# lfo.net
KiCad netlist of a schematic drawn in EAGLE
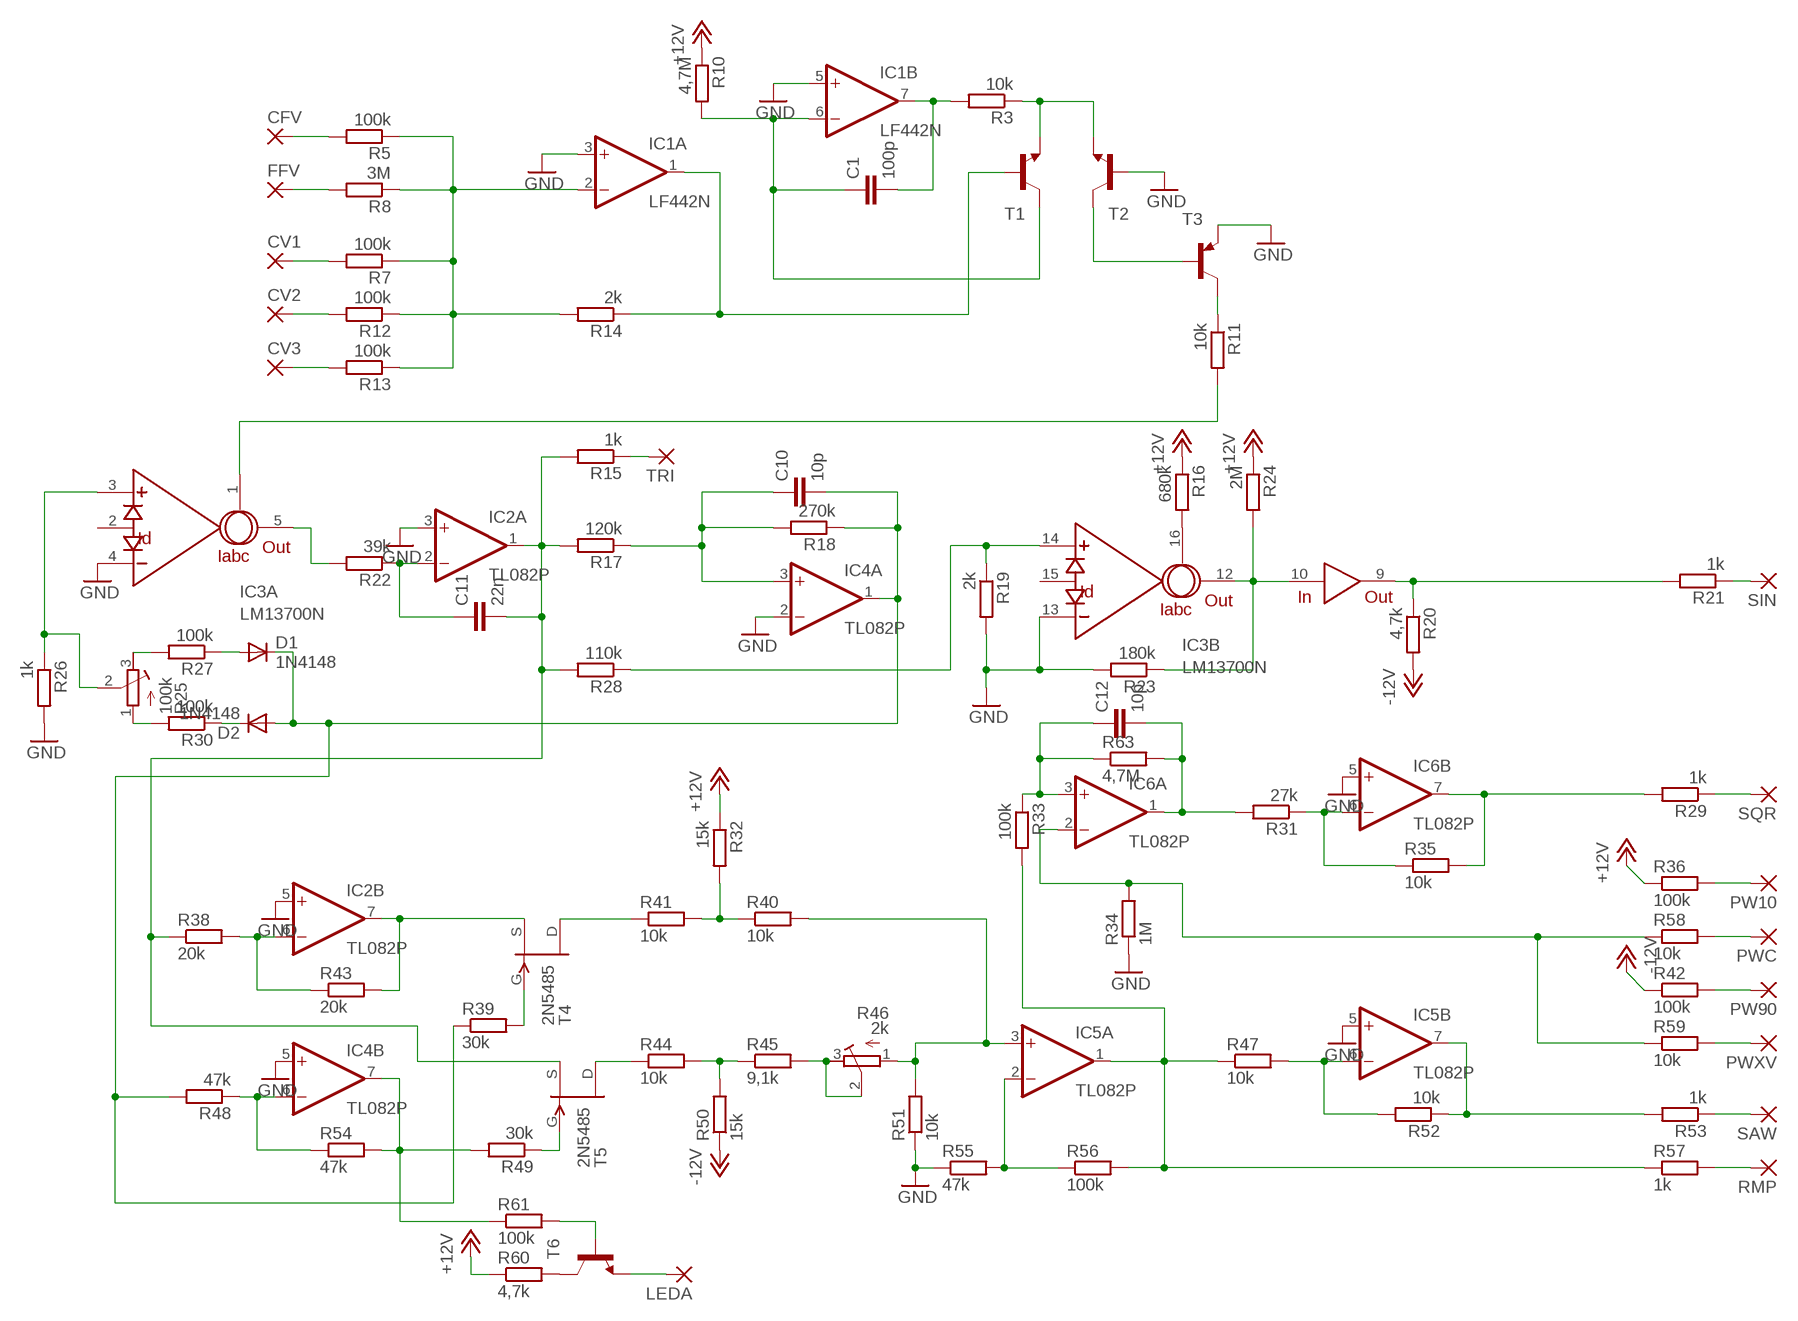
[diagram p0: schematic, sheet 1]
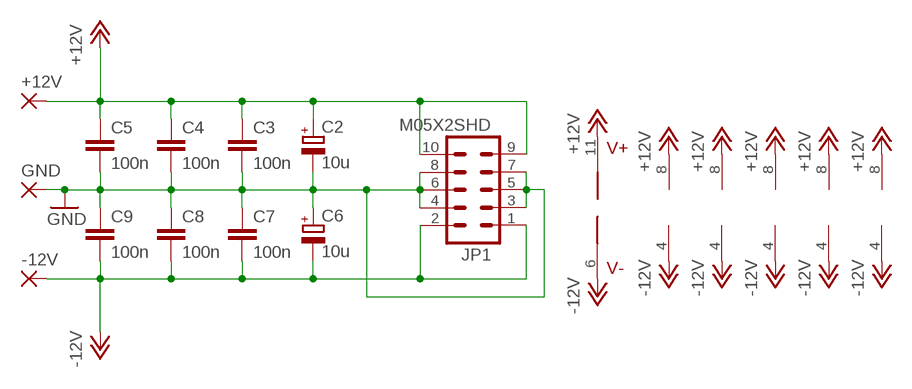
[diagram p1: schematic, sheet 2]

(export (version "E")
  (design (tool "Eeschema 10.0.6"))
  (components
    (comp (ref "+12V")
      (value "2,54/1,0")
      (footprint "eagle-import:2,54_1,0")
      (libsource (lib "eagle-import") (part "2,54/1,0"))
    )
    (comp (ref "-12V")
      (value "2,54/1,0")
      (footprint "eagle-import:2,54_1,0")
      (libsource (lib "eagle-import") (part "2,54/1,0"))
    )
    (comp (ref "C2")
      (value "10u")
      (footprint "eagle-import:E3,5-8")
      (libsource (lib "eagle-import") (part "CPOL-EUE3.5-8"))
    )
    (comp (ref "C3")
      (value "100n")
      (footprint "eagle-import:C050-035X075")
      (libsource (lib "eagle-import") (part "C-EU050-035X075"))
    )
    (comp (ref "C4")
      (value "100n")
      (footprint "eagle-import:C050-035X075")
      (libsource (lib "eagle-import") (part "C-EU050-035X075"))
    )
    (comp (ref "C5")
      (value "100n")
      (footprint "eagle-import:C050-035X075")
      (libsource (lib "eagle-import") (part "C-EU050-035X075"))
    )
    (comp (ref "C6")
      (value "10u")
      (footprint "eagle-import:E3,5-8")
      (libsource (lib "eagle-import") (part "CPOL-EUE3.5-8"))
    )
    (comp (ref "C7")
      (value "100n")
      (footprint "eagle-import:C050-035X075")
      (libsource (lib "eagle-import") (part "C-EU050-035X075"))
    )
    (comp (ref "C8")
      (value "100n")
      (footprint "eagle-import:C050-035X075")
      (libsource (lib "eagle-import") (part "C-EU050-035X075"))
    )
    (comp (ref "C9")
      (value "100n")
      (footprint "eagle-import:C050-035X075")
      (libsource (lib "eagle-import") (part "C-EU050-035X075"))
    )
    (comp (ref "GND")
      (value "2,54/1,0")
      (footprint "eagle-import:2,54_1,0")
      (libsource (lib "eagle-import") (part "2,54/1,0"))
    )
    (comp (ref "IC1")
      (value "LF442N")
      (footprint "eagle-import:DIL08")
      (libsource (lib "eagle-import") (part "LF442N"))
    )
    (comp (ref "IC2")
      (value "TL082P")
      (footprint "eagle-import:DIL08")
      (libsource (lib "eagle-import") (part "TL082P"))
    )
    (comp (ref "IC3")
      (value "LM13700N")
      (footprint "eagle-import:DIL16")
      (libsource (lib "eagle-import") (part "LM13700N"))
    )
    (comp (ref "IC4")
      (value "TL082P")
      (footprint "eagle-import:DIL08")
      (libsource (lib "eagle-import") (part "TL082P"))
    )
    (comp (ref "IC5")
      (value "TL082P")
      (footprint "eagle-import:DIL08")
      (libsource (lib "eagle-import") (part "TL082P"))
    )
    (comp (ref "IC6")
      (value "TL082P")
      (footprint "eagle-import:DIL08")
      (libsource (lib "eagle-import") (part "TL082P"))
    )
    (comp (ref "JP1")
      (value "M05X2SHD")
      (footprint "eagle-import:2X5-SHROUDED")
      (libsource (lib "eagle-import") (part "M05X2SHD"))
    )
    (comp (ref "C1")
      (value "100p")
      (footprint "eagle-import:C050-035X075")
      (libsource (lib "eagle-import") (part "C-EU050-035X075"))
    )
    (comp (ref "C10")
      (value "10p")
      (footprint "eagle-import:C050-035X075")
      (libsource (lib "eagle-import") (part "C-EU050-035X075"))
    )
    (comp (ref "C11")
      (value "22n")
      (footprint "eagle-import:C050-035X075")
      (libsource (lib "eagle-import") (part "C-EU050-035X075"))
    )
    (comp (ref "C12")
      (value "10p")
      (footprint "eagle-import:C050-035X075")
      (libsource (lib "eagle-import") (part "C-EU050-035X075"))
    )
    (comp (ref "CFV")
      (value "2,54/1,0")
      (footprint "eagle-import:2,54_1,0")
      (libsource (lib "eagle-import") (part "2,54/1,0"))
    )
    (comp (ref "CV1")
      (value "2,54/1,0")
      (footprint "eagle-import:2,54_1,0")
      (libsource (lib "eagle-import") (part "2,54/1,0"))
    )
    (comp (ref "CV2")
      (value "2,54/1,0")
      (footprint "eagle-import:2,54_1,0")
      (libsource (lib "eagle-import") (part "2,54/1,0"))
    )
    (comp (ref "CV3")
      (value "2,54/1,0")
      (footprint "eagle-import:2,54_1,0")
      (libsource (lib "eagle-import") (part "2,54/1,0"))
    )
    (comp (ref "D1")
      (value "1N4148")
      (footprint "eagle-import:DO35-7")
      (libsource (lib "eagle-import") (part "1N4148DO35-7"))
    )
    (comp (ref "D2")
      (value "1N4148")
      (footprint "eagle-import:DO35-7")
      (libsource (lib "eagle-import") (part "1N4148DO35-7"))
    )
    (comp (ref "FFV")
      (value "2,54/1,0")
      (footprint "eagle-import:2,54_1,0")
      (libsource (lib "eagle-import") (part "2,54/1,0"))
    )
    (comp (ref "LEDA")
      (value "2,54/1,0")
      (footprint "eagle-import:2,54_1,0")
      (libsource (lib "eagle-import") (part "2,54/1,0"))
    )
    (comp (ref "PW10")
      (value "2,54/1,0")
      (footprint "eagle-import:2,54_1,0")
      (libsource (lib "eagle-import") (part "2,54/1,0"))
    )
    (comp (ref "PW90")
      (value "2,54/1,0")
      (footprint "eagle-import:2,54_1,0")
      (libsource (lib "eagle-import") (part "2,54/1,0"))
    )
    (comp (ref "PWC")
      (value "2,54/1,0")
      (footprint "eagle-import:2,54_1,0")
      (libsource (lib "eagle-import") (part "2,54/1,0"))
    )
    (comp (ref "PWXV")
      (value "2,54/1,0")
      (footprint "eagle-import:2,54_1,0")
      (libsource (lib "eagle-import") (part "2,54/1,0"))
    )
    (comp (ref "R3")
      (value "10k")
      (footprint "eagle-import:0309V")
      (libsource (lib "eagle-import") (part "R-EU_0309/V"))
    )
    (comp (ref "R5")
      (value "100k")
      (footprint "eagle-import:0309V")
      (libsource (lib "eagle-import") (part "R-EU_0309/V"))
    )
    (comp (ref "R7")
      (value "100k")
      (footprint "eagle-import:0309V")
      (libsource (lib "eagle-import") (part "R-EU_0309/V"))
    )
    (comp (ref "R8")
      (value "3M")
      (footprint "eagle-import:0309V")
      (libsource (lib "eagle-import") (part "R-EU_0309/V"))
    )
    (comp (ref "R10")
      (value "4,7M")
      (footprint "eagle-import:0309V")
      (libsource (lib "eagle-import") (part "R-EU_0309/V"))
    )
    (comp (ref "R11")
      (value "10k")
      (footprint "eagle-import:0309V")
      (libsource (lib "eagle-import") (part "R-EU_0309/V"))
    )
    (comp (ref "R12")
      (value "100k")
      (footprint "eagle-import:0309V")
      (libsource (lib "eagle-import") (part "R-EU_0309/V"))
    )
    (comp (ref "R13")
      (value "100k")
      (footprint "eagle-import:0309V")
      (libsource (lib "eagle-import") (part "R-EU_0309/V"))
    )
    (comp (ref "R14")
      (value "2k")
      (footprint "eagle-import:0309V")
      (libsource (lib "eagle-import") (part "R-EU_0309/V"))
    )
    (comp (ref "R15")
      (value "1k")
      (footprint "eagle-import:0309V")
      (libsource (lib "eagle-import") (part "R-EU_0309/V"))
    )
    (comp (ref "R16")
      (value "680k")
      (footprint "eagle-import:0309V")
      (libsource (lib "eagle-import") (part "R-EU_0309/V"))
    )
    (comp (ref "R17")
      (value "120k")
      (footprint "eagle-import:0309V")
      (libsource (lib "eagle-import") (part "R-EU_0309/V"))
    )
    (comp (ref "R18")
      (value "270k")
      (footprint "eagle-import:0309V")
      (libsource (lib "eagle-import") (part "R-EU_0309/V"))
    )
    (comp (ref "R19")
      (value "2k")
      (footprint "eagle-import:0309V")
      (libsource (lib "eagle-import") (part "R-EU_0309/V"))
    )
    (comp (ref "R20")
      (value "4,7k")
      (footprint "eagle-import:0309V")
      (libsource (lib "eagle-import") (part "R-EU_0309/V"))
    )
    (comp (ref "R21")
      (value "1k")
      (footprint "eagle-import:0309V")
      (libsource (lib "eagle-import") (part "R-EU_0309/V"))
    )
    (comp (ref "R22")
      (value "39k")
      (footprint "eagle-import:0309V")
      (libsource (lib "eagle-import") (part "R-EU_0309/V"))
    )
    (comp (ref "R23")
      (value "180k")
      (footprint "eagle-import:0309V")
      (libsource (lib "eagle-import") (part "R-EU_0309/V"))
    )
    (comp (ref "R24")
      (value "2M")
      (footprint "eagle-import:0309V")
      (libsource (lib "eagle-import") (part "R-EU_0309/V"))
    )
    (comp (ref "R25")
      (value "100k")
      (footprint "eagle-import:RTRIM64W")
      (libsource (lib "eagle-import") (part "R-TRIMM64W"))
    )
    (comp (ref "R26")
      (value "1k")
      (footprint "eagle-import:0309V")
      (libsource (lib "eagle-import") (part "R-EU_0309/V"))
    )
    (comp (ref "R27")
      (value "100k")
      (footprint "eagle-import:0309V")
      (libsource (lib "eagle-import") (part "R-EU_0309/V"))
    )
    (comp (ref "R28")
      (value "110k")
      (footprint "eagle-import:0309V")
      (libsource (lib "eagle-import") (part "R-EU_0309/V"))
    )
    (comp (ref "R29")
      (value "1k")
      (footprint "eagle-import:0309V")
      (libsource (lib "eagle-import") (part "R-EU_0309/V"))
    )
    (comp (ref "R30")
      (value "100k")
      (footprint "eagle-import:0309V")
      (libsource (lib "eagle-import") (part "R-EU_0309/V"))
    )
    (comp (ref "R31")
      (value "27k")
      (footprint "eagle-import:0309V")
      (libsource (lib "eagle-import") (part "R-EU_0309/V"))
    )
    (comp (ref "R32")
      (value "15k")
      (footprint "eagle-import:0309V")
      (libsource (lib "eagle-import") (part "R-EU_0309/V"))
    )
    (comp (ref "R33")
      (value "100k")
      (footprint "eagle-import:0309V")
      (libsource (lib "eagle-import") (part "R-EU_0309/V"))
    )
    (comp (ref "R34")
      (value "1M")
      (footprint "eagle-import:0309V")
      (libsource (lib "eagle-import") (part "R-EU_0309/V"))
    )
    (comp (ref "R35")
      (value "10k")
      (footprint "eagle-import:0309V")
      (libsource (lib "eagle-import") (part "R-EU_0309/V"))
    )
    (comp (ref "R36")
      (value "100k")
      (footprint "eagle-import:0309V")
      (libsource (lib "eagle-import") (part "R-EU_0309/V"))
    )
    (comp (ref "R38")
      (value "20k")
      (footprint "eagle-import:0309V")
      (libsource (lib "eagle-import") (part "R-EU_0309/V"))
    )
    (comp (ref "R39")
      (value "30k")
      (footprint "eagle-import:0309V")
      (libsource (lib "eagle-import") (part "R-EU_0309/V"))
    )
    (comp (ref "R40")
      (value "10k")
      (footprint "eagle-import:0309V")
      (libsource (lib "eagle-import") (part "R-EU_0309/V"))
    )
    (comp (ref "R41")
      (value "10k")
      (footprint "eagle-import:0309V")
      (libsource (lib "eagle-import") (part "R-EU_0309/V"))
    )
    (comp (ref "R42")
      (value "100k")
      (footprint "eagle-import:0309V")
      (libsource (lib "eagle-import") (part "R-EU_0309/V"))
    )
    (comp (ref "R43")
      (value "20k")
      (footprint "eagle-import:0309V")
      (libsource (lib "eagle-import") (part "R-EU_0309/V"))
    )
    (comp (ref "R44")
      (value "10k")
      (footprint "eagle-import:0309V")
      (libsource (lib "eagle-import") (part "R-EU_0309/V"))
    )
    (comp (ref "R45")
      (value "9,1k")
      (footprint "eagle-import:0309V")
      (libsource (lib "eagle-import") (part "R-EU_0309/V"))
    )
    (comp (ref "R46")
      (value "2k")
      (footprint "eagle-import:RTRIM64W")
      (libsource (lib "eagle-import") (part "R-TRIMM64W"))
    )
    (comp (ref "R47")
      (value "10k")
      (footprint "eagle-import:0309V")
      (libsource (lib "eagle-import") (part "R-EU_0309/V"))
    )
    (comp (ref "R48")
      (value "47k")
      (footprint "eagle-import:0309V")
      (libsource (lib "eagle-import") (part "R-EU_0309/V"))
    )
    (comp (ref "R49")
      (value "30k")
      (footprint "eagle-import:0309V")
      (libsource (lib "eagle-import") (part "R-EU_0309/V"))
    )
    (comp (ref "R50")
      (value "15k")
      (footprint "eagle-import:0309V")
      (libsource (lib "eagle-import") (part "R-EU_0309/V"))
    )
    (comp (ref "R51")
      (value "10k")
      (footprint "eagle-import:0309V")
      (libsource (lib "eagle-import") (part "R-EU_0309/V"))
    )
    (comp (ref "R52")
      (value "10k")
      (footprint "eagle-import:0309V")
      (libsource (lib "eagle-import") (part "R-EU_0309/V"))
    )
    (comp (ref "R53")
      (value "1k")
      (footprint "eagle-import:0309V")
      (libsource (lib "eagle-import") (part "R-EU_0309/V"))
    )
    (comp (ref "R54")
      (value "47k")
      (footprint "eagle-import:0309V")
      (libsource (lib "eagle-import") (part "R-EU_0309/V"))
    )
    (comp (ref "R55")
      (value "47k")
      (footprint "eagle-import:0309V")
      (libsource (lib "eagle-import") (part "R-EU_0309/V"))
    )
    (comp (ref "R56")
      (value "100k")
      (footprint "eagle-import:0309V")
      (libsource (lib "eagle-import") (part "R-EU_0309/V"))
    )
    (comp (ref "R57")
      (value "1k")
      (footprint "eagle-import:0309V")
      (libsource (lib "eagle-import") (part "R-EU_0309/V"))
    )
    (comp (ref "R58")
      (value "10k")
      (footprint "eagle-import:0309V")
      (libsource (lib "eagle-import") (part "R-EU_0309/V"))
    )
    (comp (ref "R59")
      (value "10k")
      (footprint "eagle-import:0309V")
      (libsource (lib "eagle-import") (part "R-EU_0309/V"))
    )
    (comp (ref "R60")
      (value "4,7k")
      (footprint "eagle-import:0309V")
      (libsource (lib "eagle-import") (part "R-EU_0309/V"))
    )
    (comp (ref "R61")
      (value "100k")
      (footprint "eagle-import:0309V")
      (libsource (lib "eagle-import") (part "R-EU_0309/V"))
    )
    (comp (ref "R63")
      (value "4,7M")
      (footprint "eagle-import:0309_10")
      (libsource (lib "eagle-import") (part "R-EU_0309/10"))
    )
    (comp (ref "RMP")
      (value "2,54/1,0")
      (footprint "eagle-import:2,54_1,0")
      (libsource (lib "eagle-import") (part "2,54/1,0"))
    )
    (comp (ref "SAW")
      (value "2,54/1,0")
      (footprint "eagle-import:2,54_1,0")
      (libsource (lib "eagle-import") (part "2,54/1,0"))
    )
    (comp (ref "SIN")
      (value "2,54/1,0")
      (footprint "eagle-import:2,54_1,0")
      (libsource (lib "eagle-import") (part "2,54/1,0"))
    )
    (comp (ref "SQR")
      (value "2,54/1,0")
      (footprint "eagle-import:2,54_1,0")
      (libsource (lib "eagle-import") (part "2,54/1,0"))
    )
    (comp (ref "T1")
      (value "2N3904-NPN-TO92-EBC")
      (footprint "eagle-import:TO92-EBC")
      (libsource (lib "eagle-import") (part "-NPN-TO92-EBC2N3904"))
    )
    (comp (ref "T2")
      (value "2N3904-NPN-TO92-EBC")
      (footprint "eagle-import:TO92-EBC")
      (libsource (lib "eagle-import") (part "-NPN-TO92-EBC2N3904"))
    )
    (comp (ref "T3")
      (value "2N3906-PNP-TO92-EBC")
      (footprint "eagle-import:TO92-EBC")
      (libsource (lib "eagle-import") (part "-PNP-TO92-EBC2N3906"))
    )
    (comp (ref "T4")
      (value "2N5485")
      (footprint "eagle-import:TO92-")
      (libsource (lib "eagle-import") (part "?5482N5"))
    )
    (comp (ref "T5")
      (value "2N5485")
      (footprint "eagle-import:TO92-")
      (libsource (lib "eagle-import") (part "?5482N5"))
    )
    (comp (ref "T6")
      (value "2N3904-NPN-TO92-EBC")
      (footprint "eagle-import:TO92-EBC")
      (libsource (lib "eagle-import") (part "-NPN-TO92-EBC2N3904"))
    )
    (comp (ref "TRI")
      (value "2,54/1,0")
      (footprint "eagle-import:2,54_1,0")
      (libsource (lib "eagle-import") (part "2,54/1,0"))
    )
  )
  (nets
    (net (code "1") (name "+12V") (class "Default")
      (node (ref "+12V") (pin "1") (pinfunction "P_1") (pintype "passive"))
      (node (ref "C2") (pin "+") (pinfunction "+_+") (pintype "passive"))
      (node (ref "C3") (pin "1") (pinfunction "1_1") (pintype "passive"))
      (node (ref "C4") (pin "1") (pinfunction "1_1") (pintype "passive"))
      (node (ref "C5") (pin "1") (pinfunction "1_1") (pintype "passive"))
      (node (ref "IC1") (pin "8") (pinfunction "V+_8") (pintype "power_in"))
      (node (ref "IC2") (pin "8") (pinfunction "V+_8") (pintype "power_in"))
      (node (ref "IC3") (pin "11") (pinfunction "V+_11") (pintype "bidirectional"))
      (node (ref "IC4") (pin "8") (pinfunction "V+_8") (pintype "power_in"))
      (node (ref "IC5") (pin "8") (pinfunction "V+_8") (pintype "power_in"))
      (node (ref "IC6") (pin "8") (pinfunction "V+_8") (pintype "power_in"))
      (node (ref "JP1") (pin "10") (pinfunction "10_10") (pintype "passive"))
      (node (ref "JP1") (pin "9") (pinfunction "9_9") (pintype "passive"))
      (node (ref "R10") (pin "1") (pinfunction "1_1") (pintype "passive"))
      (node (ref "R16") (pin "1") (pinfunction "1_1") (pintype "passive"))
      (node (ref "R24") (pin "1") (pinfunction "1_1") (pintype "passive"))
      (node (ref "R32") (pin "1") (pinfunction "1_1") (pintype "passive"))
      (node (ref "R36") (pin "1") (pinfunction "1_1") (pintype "passive"))
      (node (ref "R60") (pin "1") (pinfunction "1_1") (pintype "passive"))
    )
    (net (code "2") (name "-12V") (class "Default")
      (node (ref "-12V") (pin "1") (pinfunction "P_1") (pintype "passive"))
      (node (ref "C6") (pin "-") (pinfunction "-_-") (pintype "passive"))
      (node (ref "C7") (pin "2") (pinfunction "2_2") (pintype "passive"))
      (node (ref "C8") (pin "2") (pinfunction "2_2") (pintype "passive"))
      (node (ref "C9") (pin "2") (pinfunction "2_2") (pintype "passive"))
      (node (ref "IC1") (pin "4") (pinfunction "V-_4") (pintype "power_in"))
      (node (ref "IC2") (pin "4") (pinfunction "V-_4") (pintype "power_in"))
      (node (ref "IC3") (pin "6") (pinfunction "V-_6") (pintype "bidirectional"))
      (node (ref "IC4") (pin "4") (pinfunction "V-_4") (pintype "power_in"))
      (node (ref "IC5") (pin "4") (pinfunction "V-_4") (pintype "power_in"))
      (node (ref "IC6") (pin "4") (pinfunction "V-_4") (pintype "power_in"))
      (node (ref "JP1") (pin "1") (pinfunction "1_1") (pintype "passive"))
      (node (ref "JP1") (pin "2") (pinfunction "2_2") (pintype "passive"))
      (node (ref "R20") (pin "2") (pinfunction "2_2") (pintype "passive"))
      (node (ref "R42") (pin "1") (pinfunction "1_1") (pintype "passive"))
      (node (ref "R50") (pin "1") (pinfunction "1_1") (pintype "passive"))
    )
    (net (code "3") (name "GND") (class "Default")
      (node (ref "C2") (pin "-") (pinfunction "-_-") (pintype "passive"))
      (node (ref "C3") (pin "2") (pinfunction "2_2") (pintype "passive"))
      (node (ref "C4") (pin "2") (pinfunction "2_2") (pintype "passive"))
      (node (ref "C5") (pin "2") (pinfunction "2_2") (pintype "passive"))
      (node (ref "C6") (pin "+") (pinfunction "+_+") (pintype "passive"))
      (node (ref "C7") (pin "1") (pinfunction "1_1") (pintype "passive"))
      (node (ref "C8") (pin "1") (pinfunction "1_1") (pintype "passive"))
      (node (ref "C9") (pin "1") (pinfunction "1_1") (pintype "passive"))
      (node (ref "GND") (pin "1") (pinfunction "P_1") (pintype "passive"))
      (node (ref "IC1") (pin "3") (pinfunction "+IN_3") (pintype "input"))
      (node (ref "IC1") (pin "5") (pinfunction "+IN_5") (pintype "input"))
      (node (ref "IC2") (pin "3") (pinfunction "+IN_3") (pintype "input"))
      (node (ref "IC2") (pin "5") (pinfunction "+IN_5") (pintype "input"))
      (node (ref "IC3") (pin "13") (pinfunction "-IN_13") (pintype "bidirectional"))
      (node (ref "IC3") (pin "4") (pinfunction "-IN_4") (pintype "bidirectional"))
      (node (ref "IC4") (pin "2") (pinfunction "-IN_2") (pintype "input"))
      (node (ref "IC4") (pin "5") (pinfunction "+IN_5") (pintype "input"))
      (node (ref "IC5") (pin "5") (pinfunction "+IN_5") (pintype "input"))
      (node (ref "IC6") (pin "5") (pinfunction "+IN_5") (pintype "input"))
      (node (ref "JP1") (pin "3") (pinfunction "3_3") (pintype "passive"))
      (node (ref "JP1") (pin "4") (pinfunction "4_4") (pintype "passive"))
      (node (ref "JP1") (pin "5") (pinfunction "5_5") (pintype "passive"))
      (node (ref "JP1") (pin "6") (pinfunction "6_6") (pintype "passive"))
      (node (ref "JP1") (pin "7") (pinfunction "7_7") (pintype "passive"))
      (node (ref "JP1") (pin "8") (pinfunction "8_8") (pintype "passive"))
      (node (ref "R19") (pin "2") (pinfunction "2_2") (pintype "passive"))
      (node (ref "R23") (pin "2") (pinfunction "2_2") (pintype "passive"))
      (node (ref "R26") (pin "2") (pinfunction "2_2") (pintype "passive"))
      (node (ref "R34") (pin "1") (pinfunction "1_1") (pintype "passive"))
      (node (ref "R51") (pin "1") (pinfunction "1_1") (pintype "passive"))
      (node (ref "R55") (pin "1") (pinfunction "1_1") (pintype "passive"))
      (node (ref "T2") (pin "B") (pinfunction "B_B") (pintype "passive"))
      (node (ref "T3") (pin "E") (pinfunction "E_E") (pintype "passive"))
    )
    (net (code "4") (name "Net-(CFV-P)") (class "Default")
      (node (ref "CFV") (pin "1") (pinfunction "P_1") (pintype "passive"))
      (node (ref "R5") (pin "2") (pinfunction "2_2") (pintype "passive"))
    )
    (net (code "5") (name "Net-(CV1-P)") (class "Default")
      (node (ref "CV1") (pin "1") (pinfunction "P_1") (pintype "passive"))
      (node (ref "R7") (pin "2") (pinfunction "2_2") (pintype "passive"))
    )
    (net (code "6") (name "Net-(CV2-P)") (class "Default")
      (node (ref "CV2") (pin "1") (pinfunction "P_1") (pintype "passive"))
      (node (ref "R12") (pin "2") (pinfunction "2_2") (pintype "passive"))
    )
    (net (code "7") (name "Net-(CV3-P)") (class "Default")
      (node (ref "CV3") (pin "1") (pinfunction "P_1") (pintype "passive"))
      (node (ref "R13") (pin "2") (pinfunction "2_2") (pintype "passive"))
    )
    (net (code "8") (name "Net-(D1-PadA)") (class "Default")
      (node (ref "D1") (pin "A") (pinfunction "A_A") (pintype "passive"))
      (node (ref "R27") (pin "1") (pinfunction "1_1") (pintype "passive"))
    )
    (net (code "9") (name "Net-(D2-PadC)") (class "Default")
      (node (ref "D2") (pin "C") (pinfunction "C_C") (pintype "passive"))
      (node (ref "R30") (pin "1") (pinfunction "1_1") (pintype "passive"))
    )
    (net (code "10") (name "Net-(FFV-P)") (class "Default")
      (node (ref "FFV") (pin "1") (pinfunction "P_1") (pintype "passive"))
      (node (ref "R8") (pin "2") (pinfunction "2_2") (pintype "passive"))
    )
    (net (code "11") (name "Net-(IC1A--IN)") (class "Default")
      (node (ref "IC1") (pin "2") (pinfunction "-IN_2") (pintype "input"))
      (node (ref "R12") (pin "1") (pinfunction "1_1") (pintype "passive"))
      (node (ref "R13") (pin "1") (pinfunction "1_1") (pintype "passive"))
      (node (ref "R14") (pin "2") (pinfunction "2_2") (pintype "passive"))
      (node (ref "R5") (pin "1") (pinfunction "1_1") (pintype "passive"))
      (node (ref "R7") (pin "1") (pinfunction "1_1") (pintype "passive"))
      (node (ref "R8") (pin "1") (pinfunction "1_1") (pintype "passive"))
    )
    (net (code "12") (name "Net-(IC1A-OUT)") (class "Default")
      (node (ref "IC1") (pin "1") (pinfunction "OUT_1") (pintype "output"))
      (node (ref "R14") (pin "1") (pinfunction "1_1") (pintype "passive"))
      (node (ref "T1") (pin "B") (pinfunction "B_B") (pintype "passive"))
    )
    (net (code "13") (name "Net-(IC1B--IN)") (class "Default")
      (node (ref "C1") (pin "1") (pinfunction "1_1") (pintype "passive"))
      (node (ref "IC1") (pin "6") (pinfunction "-IN_6") (pintype "input"))
      (node (ref "R10") (pin "2") (pinfunction "2_2") (pintype "passive"))
      (node (ref "T1") (pin "C") (pinfunction "C_C") (pintype "passive"))
    )
    (net (code "14") (name "Net-(IC1B-OUT)") (class "Default")
      (node (ref "C1") (pin "2") (pinfunction "2_2") (pintype "passive"))
      (node (ref "IC1") (pin "7") (pinfunction "OUT_7") (pintype "output"))
      (node (ref "R3") (pin "2") (pinfunction "2_2") (pintype "passive"))
    )
    (net (code "15") (name "Net-(IC2A--IN)") (class "Default")
      (node (ref "C11") (pin "1") (pinfunction "1_1") (pintype "passive"))
      (node (ref "IC2") (pin "2") (pinfunction "-IN_2") (pintype "input"))
      (node (ref "R22") (pin "1") (pinfunction "1_1") (pintype "passive"))
    )
    (net (code "16") (name "Net-(IC2A-OUT)") (class "Default")
      (node (ref "C11") (pin "2") (pinfunction "2_2") (pintype "passive"))
      (node (ref "IC2") (pin "1") (pinfunction "OUT_1") (pintype "output"))
      (node (ref "R15") (pin "2") (pinfunction "2_2") (pintype "passive"))
      (node (ref "R17") (pin "2") (pinfunction "2_2") (pintype "passive"))
      (node (ref "R28") (pin "2") (pinfunction "2_2") (pintype "passive"))
      (node (ref "R38") (pin "1") (pinfunction "1_1") (pintype "passive"))
      (node (ref "T5") (pin "2") (pinfunction "S_2") (pintype "passive"))
    )
    (net (code "17") (name "Net-(IC2B--IN)") (class "Default")
      (node (ref "IC2") (pin "6") (pinfunction "-IN_6") (pintype "input"))
      (node (ref "R38") (pin "2") (pinfunction "2_2") (pintype "passive"))
      (node (ref "R43") (pin "1") (pinfunction "1_1") (pintype "passive"))
    )
    (net (code "18") (name "Net-(IC2B-OUT)") (class "Default")
      (node (ref "IC2") (pin "7") (pinfunction "OUT_7") (pintype "output"))
      (node (ref "R43") (pin "2") (pinfunction "2_2") (pintype "passive"))
      (node (ref "T4") (pin "2") (pinfunction "S_2") (pintype "passive"))
    )
    (net (code "19") (name "Net-(IC3A-+IN)") (class "Default")
      (node (ref "IC3") (pin "3") (pinfunction "+IN_3") (pintype "bidirectional"))
      (node (ref "R25") (pin "2") (pinfunction "S_2") (pintype "passive"))
      (node (ref "R26") (pin "1") (pinfunction "1_1") (pintype "passive"))
    )
    (net (code "20") (name "Net-(IC3A-IABC)") (class "Default")
      (node (ref "IC3") (pin "1") (pinfunction "IABC_1") (pintype "bidirectional"))
      (node (ref "R11") (pin "2") (pinfunction "2_2") (pintype "passive"))
    )
    (net (code "21") (name "Net-(IC3A-OUT)") (class "Default")
      (node (ref "IC3") (pin "5") (pinfunction "OUT_5") (pintype "bidirectional"))
      (node (ref "R22") (pin "2") (pinfunction "2_2") (pintype "passive"))
    )
    (net (code "22") (name "Net-(IC3B-+IN)") (class "Default")
      (node (ref "IC3") (pin "14") (pinfunction "+IN_14") (pintype "bidirectional"))
      (node (ref "R19") (pin "1") (pinfunction "1_1") (pintype "passive"))
      (node (ref "R28") (pin "1") (pinfunction "1_1") (pintype "passive"))
    )
    (net (code "23") (name "Net-(IC3B-IABC)") (class "Default")
      (node (ref "IC3") (pin "16") (pinfunction "IABC_16") (pintype "bidirectional"))
      (node (ref "R16") (pin "2") (pinfunction "2_2") (pintype "passive"))
    )
    (net (code "24") (name "Net-(IC3B-OUT)") (class "Default")
      (node (ref "IC3") (pin "10") (pinfunction "IN_10") (pintype "bidirectional"))
      (node (ref "IC3") (pin "12") (pinfunction "OUT_12") (pintype "bidirectional"))
      (node (ref "R23") (pin "1") (pinfunction "1_1") (pintype "passive"))
      (node (ref "R24") (pin "2") (pinfunction "2_2") (pintype "passive"))
    )
    (net (code "25") (name "Net-(IC3D-OUT)") (class "Default")
      (node (ref "IC3") (pin "9") (pinfunction "OUT_9") (pintype "bidirectional"))
      (node (ref "R20") (pin "1") (pinfunction "1_1") (pintype "passive"))
      (node (ref "R21") (pin "2") (pinfunction "2_2") (pintype "passive"))
    )
    (net (code "26") (name "Net-(IC4A-+IN)") (class "Default")
      (node (ref "C10") (pin "1") (pinfunction "1_1") (pintype "passive"))
      (node (ref "IC4") (pin "3") (pinfunction "+IN_3") (pintype "input"))
      (node (ref "R17") (pin "1") (pinfunction "1_1") (pintype "passive"))
      (node (ref "R18") (pin "2") (pinfunction "2_2") (pintype "passive"))
    )
    (net (code "27") (name "Net-(IC4A-OUT)") (class "Default")
      (node (ref "C10") (pin "2") (pinfunction "2_2") (pintype "passive"))
      (node (ref "D1") (pin "C") (pinfunction "C_C") (pintype "passive"))
      (node (ref "D2") (pin "A") (pinfunction "A_A") (pintype "passive"))
      (node (ref "IC4") (pin "1") (pinfunction "OUT_1") (pintype "output"))
      (node (ref "R18") (pin "1") (pinfunction "1_1") (pintype "passive"))
      (node (ref "R39") (pin "1") (pinfunction "1_1") (pintype "passive"))
      (node (ref "R48") (pin "2") (pinfunction "2_2") (pintype "passive"))
    )
    (net (code "28") (name "Net-(IC4B--IN)") (class "Default")
      (node (ref "IC4") (pin "6") (pinfunction "-IN_6") (pintype "input"))
      (node (ref "R48") (pin "1") (pinfunction "1_1") (pintype "passive"))
      (node (ref "R54") (pin "1") (pinfunction "1_1") (pintype "passive"))
    )
    (net (code "29") (name "Net-(IC4B-OUT)") (class "Default")
      (node (ref "IC4") (pin "7") (pinfunction "OUT_7") (pintype "output"))
      (node (ref "R49") (pin "2") (pinfunction "2_2") (pintype "passive"))
      (node (ref "R54") (pin "2") (pinfunction "2_2") (pintype "passive"))
      (node (ref "R61") (pin "1") (pinfunction "1_1") (pintype "passive"))
    )
    (net (code "30") (name "Net-(IC5A-+IN)") (class "Default")
      (node (ref "IC5") (pin "3") (pinfunction "+IN_3") (pintype "input"))
      (node (ref "R40") (pin "2") (pinfunction "2_2") (pintype "passive"))
      (node (ref "R46") (pin "1") (pinfunction "A_1") (pintype "passive"))
      (node (ref "R51") (pin "2") (pinfunction "2_2") (pintype "passive"))
    )
    (net (code "31") (name "Net-(IC5A--IN)") (class "Default")
      (node (ref "IC5") (pin "2") (pinfunction "-IN_2") (pintype "input"))
      (node (ref "R55") (pin "2") (pinfunction "2_2") (pintype "passive"))
      (node (ref "R56") (pin "1") (pinfunction "1_1") (pintype "passive"))
    )
    (net (code "32") (name "Net-(IC5A-OUT)") (class "Default")
      (node (ref "IC5") (pin "1") (pinfunction "OUT_1") (pintype "output"))
      (node (ref "R33") (pin "2") (pinfunction "2_2") (pintype "passive"))
      (node (ref "R47") (pin "1") (pinfunction "1_1") (pintype "passive"))
      (node (ref "R56") (pin "2") (pinfunction "2_2") (pintype "passive"))
      (node (ref "R57") (pin "1") (pinfunction "1_1") (pintype "passive"))
    )
    (net (code "33") (name "Net-(IC5B--IN)") (class "Default")
      (node (ref "IC5") (pin "6") (pinfunction "-IN_6") (pintype "input"))
      (node (ref "R47") (pin "2") (pinfunction "2_2") (pintype "passive"))
      (node (ref "R52") (pin "2") (pinfunction "2_2") (pintype "passive"))
    )
    (net (code "34") (name "Net-(IC5B-OUT)") (class "Default")
      (node (ref "IC5") (pin "7") (pinfunction "OUT_7") (pintype "output"))
      (node (ref "R52") (pin "1") (pinfunction "1_1") (pintype "passive"))
      (node (ref "R53") (pin "2") (pinfunction "2_2") (pintype "passive"))
    )
    (net (code "35") (name "Net-(IC6A-+IN)") (class "Default")
      (node (ref "C12") (pin "1") (pinfunction "1_1") (pintype "passive"))
      (node (ref "IC6") (pin "3") (pinfunction "+IN_3") (pintype "input"))
      (node (ref "R33") (pin "1") (pinfunction "1_1") (pintype "passive"))
      (node (ref "R63") (pin "1") (pinfunction "1_1") (pintype "passive"))
    )
    (net (code "36") (name "Net-(IC6A--IN)") (class "Default")
      (node (ref "IC6") (pin "2") (pinfunction "-IN_2") (pintype "input"))
      (node (ref "R34") (pin "2") (pinfunction "2_2") (pintype "passive"))
      (node (ref "R58") (pin "1") (pinfunction "1_1") (pintype "passive"))
      (node (ref "R59") (pin "1") (pinfunction "1_1") (pintype "passive"))
    )
    (net (code "37") (name "Net-(IC6A-OUT)") (class "Default")
      (node (ref "C12") (pin "2") (pinfunction "2_2") (pintype "passive"))
      (node (ref "IC6") (pin "1") (pinfunction "OUT_1") (pintype "output"))
      (node (ref "R31") (pin "2") (pinfunction "2_2") (pintype "passive"))
      (node (ref "R63") (pin "2") (pinfunction "2_2") (pintype "passive"))
    )
    (net (code "38") (name "Net-(IC6B--IN)") (class "Default")
      (node (ref "IC6") (pin "6") (pinfunction "-IN_6") (pintype "input"))
      (node (ref "R31") (pin "1") (pinfunction "1_1") (pintype "passive"))
      (node (ref "R35") (pin "1") (pinfunction "1_1") (pintype "passive"))
    )
    (net (code "39") (name "Net-(IC6B-OUT)") (class "Default")
      (node (ref "IC6") (pin "7") (pinfunction "OUT_7") (pintype "output"))
      (node (ref "R29") (pin "2") (pinfunction "2_2") (pintype "passive"))
      (node (ref "R35") (pin "2") (pinfunction "2_2") (pintype "passive"))
    )
    (net (code "40") (name "Net-(LEDA-P)") (class "Default")
      (node (ref "LEDA") (pin "1") (pinfunction "P_1") (pintype "passive"))
      (node (ref "T6") (pin "E") (pinfunction "E_E") (pintype "passive"))
    )
    (net (code "41") (name "Net-(PW10-P)") (class "Default")
      (node (ref "PW10") (pin "1") (pinfunction "P_1") (pintype "passive"))
      (node (ref "R36") (pin "2") (pinfunction "2_2") (pintype "passive"))
    )
    (net (code "42") (name "Net-(PW90-P)") (class "Default")
      (node (ref "PW90") (pin "1") (pinfunction "P_1") (pintype "passive"))
      (node (ref "R42") (pin "2") (pinfunction "2_2") (pintype "passive"))
    )
    (net (code "43") (name "Net-(PWC-P)") (class "Default")
      (node (ref "PWC") (pin "1") (pinfunction "P_1") (pintype "passive"))
      (node (ref "R58") (pin "2") (pinfunction "2_2") (pintype "passive"))
    )
    (net (code "44") (name "Net-(PWXV-P)") (class "Default")
      (node (ref "PWXV") (pin "1") (pinfunction "P_1") (pintype "passive"))
      (node (ref "R59") (pin "2") (pinfunction "2_2") (pintype "passive"))
    )
    (net (code "45") (name "Net-(R3-Pad1)") (class "Default")
      (node (ref "R3") (pin "1") (pinfunction "1_1") (pintype "passive"))
      (node (ref "T1") (pin "E") (pinfunction "E_E") (pintype "passive"))
      (node (ref "T2") (pin "E") (pinfunction "E_E") (pintype "passive"))
    )
    (net (code "46") (name "Net-(R11-Pad1)") (class "Default")
      (node (ref "R11") (pin "1") (pinfunction "1_1") (pintype "passive"))
      (node (ref "T3") (pin "C") (pinfunction "C_C") (pintype "passive"))
    )
    (net (code "47") (name "Net-(R25-A)") (class "Default")
      (node (ref "R25") (pin "1") (pinfunction "A_1") (pintype "passive"))
      (node (ref "R30") (pin "2") (pinfunction "2_2") (pintype "passive"))
    )
    (net (code "48") (name "Net-(R25-E)") (class "Default")
      (node (ref "R25") (pin "3") (pinfunction "E_3") (pintype "passive"))
      (node (ref "R27") (pin "2") (pinfunction "2_2") (pintype "passive"))
    )
    (net (code "49") (name "Net-(R32-Pad2)") (class "Default")
      (node (ref "R32") (pin "2") (pinfunction "2_2") (pintype "passive"))
      (node (ref "R40") (pin "1") (pinfunction "1_1") (pintype "passive"))
      (node (ref "R41") (pin "2") (pinfunction "2_2") (pintype "passive"))
    )
    (net (code "50") (name "Net-(R44-Pad2)") (class "Default")
      (node (ref "R44") (pin "2") (pinfunction "2_2") (pintype "passive"))
      (node (ref "R45") (pin "1") (pinfunction "1_1") (pintype "passive"))
      (node (ref "R50") (pin "2") (pinfunction "2_2") (pintype "passive"))
    )
    (net (code "51") (name "Net-(R46-E)") (class "Default")
      (node (ref "R45") (pin "2") (pinfunction "2_2") (pintype "passive"))
      (node (ref "R46") (pin "2") (pinfunction "S_2") (pintype "passive"))
      (node (ref "R46") (pin "3") (pinfunction "E_3") (pintype "passive"))
    )
    (net (code "52") (name "Net-(R60-Pad2)") (class "Default")
      (node (ref "R60") (pin "2") (pinfunction "2_2") (pintype "passive"))
      (node (ref "T6") (pin "C") (pinfunction "C_C") (pintype "passive"))
    )
    (net (code "53") (name "Net-(R61-Pad2)") (class "Default")
      (node (ref "R61") (pin "2") (pinfunction "2_2") (pintype "passive"))
      (node (ref "T6") (pin "B") (pinfunction "B_B") (pintype "passive"))
    )
    (net (code "54") (name "Net-(RMP-P)") (class "Default")
      (node (ref "R57") (pin "2") (pinfunction "2_2") (pintype "passive"))
      (node (ref "RMP") (pin "1") (pinfunction "P_1") (pintype "passive"))
    )
    (net (code "55") (name "Net-(SAW-P)") (class "Default")
      (node (ref "R53") (pin "1") (pinfunction "1_1") (pintype "passive"))
      (node (ref "SAW") (pin "1") (pinfunction "P_1") (pintype "passive"))
    )
    (net (code "56") (name "Net-(SIN-P)") (class "Default")
      (node (ref "R21") (pin "1") (pinfunction "1_1") (pintype "passive"))
      (node (ref "SIN") (pin "1") (pinfunction "P_1") (pintype "passive"))
    )
    (net (code "57") (name "Net-(SQR-P)") (class "Default")
      (node (ref "R29") (pin "1") (pinfunction "1_1") (pintype "passive"))
      (node (ref "SQR") (pin "1") (pinfunction "P_1") (pintype "passive"))
    )
    (net (code "58") (name "Net-(T2-PadC)") (class "Default")
      (node (ref "T2") (pin "C") (pinfunction "C_C") (pintype "passive"))
      (node (ref "T3") (pin "B") (pinfunction "B_B") (pintype "passive"))
    )
    (net (code "59") (name "Net-(T4-D)") (class "Default")
      (node (ref "R41") (pin "1") (pinfunction "1_1") (pintype "passive"))
      (node (ref "T4") (pin "3") (pinfunction "D_3") (pintype "passive"))
    )
    (net (code "60") (name "Net-(T4-G)") (class "Default")
      (node (ref "R39") (pin "2") (pinfunction "2_2") (pintype "passive"))
      (node (ref "T4") (pin "1") (pinfunction "G_1") (pintype "passive"))
    )
    (net (code "61") (name "Net-(T5-D)") (class "Default")
      (node (ref "R44") (pin "1") (pinfunction "1_1") (pintype "passive"))
      (node (ref "T5") (pin "3") (pinfunction "D_3") (pintype "passive"))
    )
    (net (code "62") (name "Net-(T5-G)") (class "Default")
      (node (ref "R49") (pin "1") (pinfunction "1_1") (pintype "passive"))
      (node (ref "T5") (pin "1") (pinfunction "G_1") (pintype "passive"))
    )
    (net (code "63") (name "Net-(TRI-P)") (class "Default")
      (node (ref "R15") (pin "1") (pinfunction "1_1") (pintype "passive"))
      (node (ref "TRI") (pin "1") (pinfunction "P_1") (pintype "passive"))
    )
    (net (code "64") (name "unconnected-(IC3A-ID-Pad2)") (class "Default")
      (node (ref "IC3") (pin "2") (pinfunction "ID_2") (pintype "bidirectional"))
    )
    (net (code "65") (name "unconnected-(IC3B-ID-Pad15)") (class "Default")
      (node (ref "IC3") (pin "15") (pinfunction "ID_15") (pintype "bidirectional"))
    )
  )
)
